# CH3-Input.net
KiCad netlist of a schematic drawn in Altium Designer
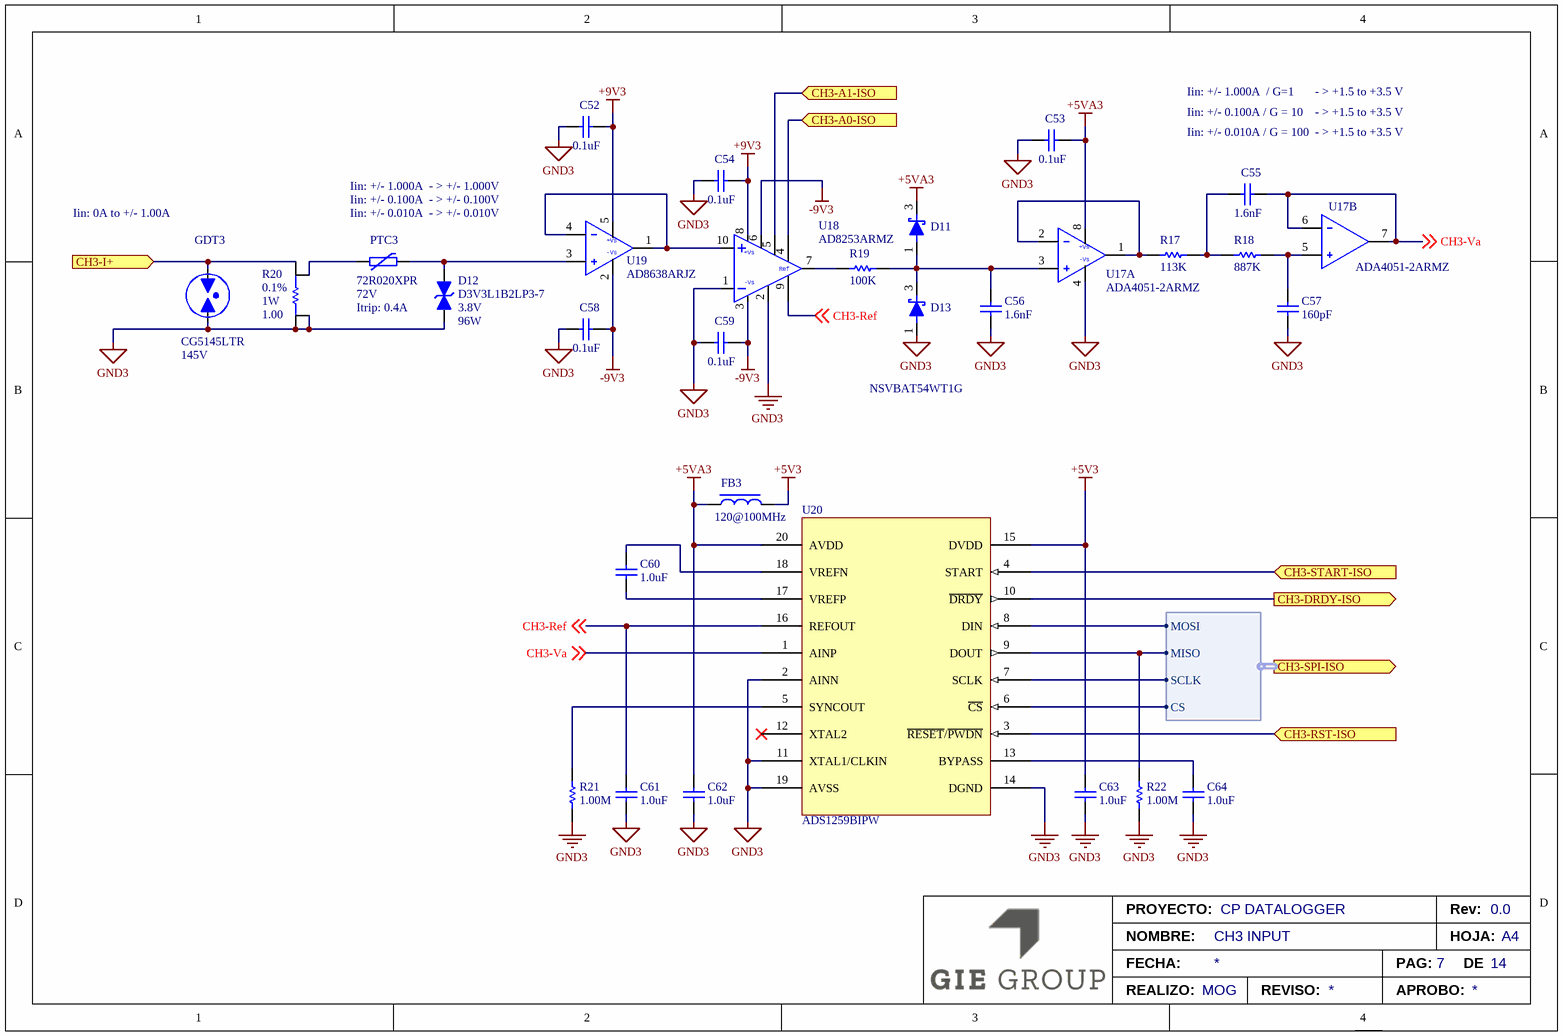
[diagram p0: CH3-Input.SchDoc]

(export (version "E")
  (design (tool "Eeschema 10.0.6"))
  (components
    (comp (ref "C52")
      (value "0.1uF")
      (footprint "CAP-0603")
      (description "CAP CER 0.1uF 50V X7R 0603")
      (fields (field (name "PARTNUMBER") "C0603C104K5RACAUTO") (field (name "MANUFACTURER") "Kemet"))
      (libsource (lib "Kemet") (part "C0603C104K5RACAUTO"))
    )
    (comp (ref "C53")
      (value "0.1uF")
      (footprint "CAP-0603")
      (description "CAP CER 0.1uF 50V X7R 0603")
      (fields (field (name "PARTNUMBER") "C0603C104K5RACAUTO") (field (name "MANUFACTURER") "Kemet"))
      (libsource (lib "Kemet") (part "C0603C104K5RACAUTO"))
    )
    (comp (ref "C54")
      (value "0.1uF")
      (footprint "CAP-0603")
      (description "CAP CER 0.1uF 50V X7R 0603")
      (fields (field (name "PARTNUMBER") "C0603C104K5RACAUTO") (field (name "MANUFACTURER") "Kemet"))
      (libsource (lib "Kemet") (part "C0603C104K5RACAUTO"))
    )
    (comp (ref "C55")
      (value "1.6nF")
      (footprint "CAP-0603")
      (description "CAP CER 1600´pF 50V C0G 0603")
      (fields (field (name "PARTNUMBER") "C0603C162J5GAC7867") (field (name "MANUFACTURER") "Kemet"))
      (libsource (lib "Kemet") (part "C0603C162J5GAC7867"))
    )
    (comp (ref "C56")
      (value "1.6nF")
      (footprint "CAP-0603")
      (description "CAP CER 1600´pF 50V C0G 0603")
      (fields (field (name "PARTNUMBER") "C0603C162J5GAC7867") (field (name "MANUFACTURER") "Kemet"))
      (libsource (lib "Kemet") (part "C0603C162J5GAC7867"))
    )
    (comp (ref "C57")
      (value "160pF")
      (footprint "CAP-0603")
      (description "CAP CER 160 pF 100V C0G 0603")
      (fields (field (name "PARTNUMBER") "C0603C161J1GAC7867") (field (name "MANUFACTURER") "Kemet"))
      (libsource (lib "Kemet") (part "C0603C161J1GAC7867"))
    )
    (comp (ref "C58")
      (value "0.1uF")
      (footprint "CAP-0603")
      (description "CAP CER 0.1uF 50V X7R 0603")
      (fields (field (name "PARTNUMBER") "C0603C104K5RACAUTO") (field (name "MANUFACTURER") "Kemet"))
      (libsource (lib "Kemet") (part "C0603C104K5RACAUTO"))
    )
    (comp (ref "C59")
      (value "0.1uF")
      (footprint "CAP-0603")
      (description "CAP CER 0.1uF 50V X7R 0603")
      (fields (field (name "PARTNUMBER") "C0603C104K5RACAUTO") (field (name "MANUFACTURER") "Kemet"))
      (libsource (lib "Kemet") (part "C0603C104K5RACAUTO"))
    )
    (comp (ref "C60")
      (value "1.0uF")
      (footprint "CAP-0603")
      (description "CAP CER 1uF 25V X7R 0603")
      (fields (field (name "PARTNUMBER") "C0603C105M3RAC7867") (field (name "MANUFACTURER") "Kemet"))
      (libsource (lib "Kemet") (part "C0603C105M3RAC7867"))
    )
    (comp (ref "C61")
      (value "1.0uF")
      (footprint "CAP-0603")
      (description "CAP CER 1uF 25V X7R 0603")
      (fields (field (name "PARTNUMBER") "C0603C105M3RAC7867") (field (name "MANUFACTURER") "Kemet"))
      (libsource (lib "Kemet") (part "C0603C105M3RAC7867"))
    )
    (comp (ref "C62")
      (value "1.0uF")
      (footprint "CAP-0603")
      (description "CAP CER 1uF 25V X7R 0603")
      (fields (field (name "PARTNUMBER") "C0603C105M3RAC7867") (field (name "MANUFACTURER") "Kemet"))
      (libsource (lib "Kemet") (part "C0603C105M3RAC7867"))
    )
    (comp (ref "C63")
      (value "1.0uF")
      (footprint "CAP-0603")
      (description "CAP CER 1uF 25V X7R 0603")
      (fields (field (name "PARTNUMBER") "C0603C105M3RAC7867") (field (name "MANUFACTURER") "Kemet"))
      (libsource (lib "Kemet") (part "C0603C105M3RAC7867"))
    )
    (comp (ref "C64")
      (value "1.0uF")
      (footprint "CAP-0603")
      (description "CAP CER 1uF 25V X7R 0603")
      (fields (field (name "PARTNUMBER") "C0603C105M3RAC7867") (field (name "MANUFACTURER") "Kemet"))
      (libsource (lib "Kemet") (part "C0603C105M3RAC7867"))
    )
    (comp (ref "D11")
      (value "NSVBAT54WT1G")
      (footprint "SOT-323-3")
      (description "Schottky Diode 30V 200mA SOT323")
      (fields (field (name "MANUFACTURER") "OnSemiconductor"))
      (libsource (lib "OnSemiconductors") (part "NSVBAT54WT1G"))
    )
    (comp (ref "D12")
      (value "D3V3L1B2LP3-7")
      (footprint "DIODE-0603")
      (description "TVS Diode 1.5kW 130V 5% Bi-Directional")
      (fields
        (field (name "MANUFACTURER") "Diodes Inc")
        (field (name "PARTNUMBER") "D3V3L1B2LP3-7")
        (field (name "VOLTAGE") "3.8V")
        (field (name "POWER") "96W")
      )
      (libsource (lib "DidesInc") (part "D3V3L1B2LP3-7"))
    )
    (comp (ref "D13")
      (value "NSVBAT54WT1G")
      (footprint "SOT-323-3")
      (description "Schottky Diode 30V 200mA SOT323")
      (fields (field (name "MANUFACTURER") "OnSemiconductor") (field (name "PARTNUMBER") "NSVBAT54WT1G"))
      (libsource (lib "OnSemiconductors") (part "NSVBAT54WT1G"))
    )
    (comp (ref "FB3")
      (value "120@100MHz")
      (footprint "IND-0603")
      (description "Ferrite Bead 120Ohms 900mA 25% DCR=130m")
      (fields (field (name "MANUFACTURER") "Kemet") (field (name "PARTNUMBER") "Z0603C121GPWZT"))
      (libsource (lib "Kemet") (part "Z0603C121GPWZT"))
    )
    (comp (ref "GDT3")
      (value "CG5145LTR")
      (footprint "LITTLELFUSE-CG5XXXLTR")
      (description "Gas Discharge Tube 145V")
      (fields
        (field (name "MANUFACTURER") "Littelfuse")
        (field (name "PARTNUMBER") "CG5145LTR")
        (field (name "VOLTAGE") "145V")
      )
      (libsource (lib "Littlelfuse") (part "CG5145LTR"))
    )
    (comp (ref "PTC3")
      (value "72R020XPR")
      (footprint "LITTLELFUSE-72R020X")
      (description "PTC Polyfuse Radial 72V 0.2A")
      (fields
        (field (name "MANUFACTURER") "Littlelfuse")
        (field (name "PARTNUMBER") "72R020XPR")
        (field (name "VOLTAGE") "72V")
        (field (name "ITRIP") "0.4A")
      )
      (libsource (lib "Littlelfuse") (part "72R020XPR"))
    )
    (comp (ref "R17")
      (value "113K")
      (footprint "RES-0603")
      (description "RES SMD 113K OHM 1% 1/10W 0603")
      (fields (field (name "TOLERANCE") "1%") (field (name "MANUFACTURER") "Yageo"))
      (libsource (lib "Yageo") (part "RC0603FR-07113KL"))
    )
    (comp (ref "R18")
      (value "887K")
      (footprint "RES-0603")
      (description "RES SMD 887K OHM 1% 1/10W 0603")
      (fields (field (name "TOLERANCE") "1%") (field (name "MANUFACTURER") "Yageo"))
      (libsource (lib "Yageo") (part "RC0603FR-07887KL"))
    )
    (comp (ref "R19")
      (value "100K")
      (footprint "RES-0603")
      (description "RES SMD 100K OHM 1% 1/10W 0603")
      (fields (field (name "TOLERANCE") "1%") (field (name "MANUFACTURER") "Yageo"))
      (libsource (lib "Yageo") (part "RC0603FR-07100KL"))
    )
    (comp (ref "R20")
      (value "1.00")
      (footprint "RES-2512 WIDE")
      (description "RES SMD 1 OHM 1W 2516 WIDE")
      (fields
        (field (name "MANUFACTURER") "Vishay")
        (field (name "PARTNUMBER") "Y16061R00000B9W")
        (field (name "TOLERANCE") "0.1%")
        (field (name "POWER") "1W")
      )
      (libsource (lib "Vishay") (part "Y16061R00000B9W"))
    )
    (comp (ref "R21")
      (value "1.00M")
      (footprint "RES-0603")
      (description "RES SMD 1M OHM 1% 1/10W 0603")
      (fields (field (name "TOLERANCE") "1%") (field (name "MANUFACTURER") "Yageo"))
      (libsource (lib "Yageo") (part "RC0603FR-071ML"))
    )
    (comp (ref "R22")
      (value "1.00M")
      (footprint "RES-0603")
      (description "RES SMD 1M OHM 1% 1/10W 0603")
      (fields (field (name "TOLERANCE") "1%") (field (name "MANUFACTURER") "Yageo"))
      (libsource (lib "Yageo") (part "RC0603FR-071ML"))
    )
    (comp (ref "U17")
      (value "ADA4051-2ARMZ")
      (footprint "MSOP8")
      (description "Dual  Precision Amplifier Micro Power Auto Zero")
      (fields (field (name "MANUFACTURER") "Analog Devices") (field (name "PARTNUMBER") "ADA4051-2ARMZ"))
      (libsource (lib "AnalogDevices") (part "ADA4051-2ARMZ"))
    )
    (comp (ref "U18")
      (value "AD8253ARMZ")
      (footprint "MSOP10")
      (description "Instrumentation Amplifiers High Speed Programmable High Gain In-Amp")
      (fields (field (name "MANUFACTURER") "Analog Devices Inc"))
      (libsource (lib "AnalogDevices") (part "AD8253ARMZ"))
    )
    (comp (ref "U19")
      (value "AD8638ARJZ")
      (footprint "SOT23-5")
      (description "16V Auto-Zero CMOS Amplifier")
      (fields (field (name "MANUFACTURER") "Analog Devices") (field (name "PARTNUMBER") "AD8638ARJZ"))
      (libsource (lib "AnalogDevices") (part "AD8638ARJZ"))
    )
    (comp (ref "U20")
      (value "ADS1259BIPW")
      (footprint "TSSOP20")
      (description "Analog to Digital Converter 14.4kSPS 24-Bit")
      (fields (field (name "MANUFACTURER") "Texas Instruments") (field (name "PARTNUMBER") "ADS1259BIPW"))
      (libsource (lib "TexasInstruments") (part "ADS1259BIPW"))
    )
  )
  (nets
    (net (code "2") (name "+5V3") (class "Default")
      (node (ref "C63") (pin "2") (pinfunction "2_2") (pintype "passive"))
      (node (ref "FB3") (pin "2") (pinfunction "2_2") (pintype "passive"))
      (node (ref "U20") (pin "15") (pinfunction "DVDD_15") (pintype "power_in"))
    )
    (net (code "3") (name "+5VA3") (class "Default")
      (node (ref "C53") (pin "2") (pinfunction "2_2") (pintype "passive"))
      (node (ref "C62") (pin "2") (pinfunction "2_2") (pintype "passive"))
      (node (ref "D11") (pin "3") (pinfunction "K_3") (pintype "passive"))
      (node (ref "FB3") (pin "1") (pinfunction "1_1") (pintype "passive"))
      (node (ref "U17") (pin "8") (pinfunction "+VS_8") (pintype "power_in"))
      (node (ref "U20") (pin "20") (pinfunction "AVDD_20") (pintype "power_in"))
    )
    (net (code "4") (name "+9V3") (class "Default")
      (node (ref "C52") (pin "2") (pinfunction "2_2") (pintype "passive"))
      (node (ref "C54") (pin "2") (pinfunction "2_2") (pintype "passive"))
      (node (ref "U18") (pin "8") (pinfunction "+Vs_8") (pintype "passive"))
      (node (ref "U19") (pin "5") (pinfunction "+VS_5") (pintype "power_in"))
    )
    (net (code "5") (name "-9V3") (class "Default")
      (node (ref "C58") (pin "2") (pinfunction "2_2") (pintype "passive"))
      (node (ref "C59") (pin "2") (pinfunction "2_2") (pintype "passive"))
      (node (ref "U18") (pin "3") (pinfunction "-Vs_3") (pintype "passive"))
      (node (ref "U18") (pin "6") (pinfunction "WR_6") (pintype "passive"))
      (node (ref "U19") (pin "2") (pinfunction "-Vs_2") (pintype "power_in"))
    )
    (net (code "6") (name "/CH3-A0-ISO") (class "Default")
      (node (ref "U18") (pin "4") (pinfunction "A0_4") (pintype "passive"))
    )
    (net (code "7") (name "/CH3-A1-ISO") (class "Default")
      (node (ref "U18") (pin "5") (pinfunction "A1_5") (pintype "passive"))
    )
    (net (code "8") (name "/CH3-DRDY-ISO") (class "Default")
      (node (ref "U20") (pin "10") (pinfunction "~{DRDY}_10") (pintype "output"))
    )
    (net (code "9") (name "/CH3-I+") (class "Default")
      (node (ref "GDT3") (pin "1") (pinfunction "A_1") (pintype "passive"))
      (node (ref "R20") (pin "I1") (pinfunction "1_I1") (pintype "passive"))
    )
    (net (code "10") (name "/CH3-RST-ISO") (class "Default")
      (node (ref "U20") (pin "3") (pinfunction "~{RESET}/~{PWDN}_3") (pintype "input"))
    )
    (net (code "11") (name "/CH3-START-ISO") (class "Default")
      (node (ref "U20") (pin "4") (pinfunction "START_4") (pintype "input"))
    )
    (net (code "12") (name "/CS") (class "Default")
      (node (ref "U20") (pin "6") (pinfunction "~{CS}_6") (pintype "input"))
    )
    (net (code "13") (name "/MISO") (class "Default")
      (node (ref "R22") (pin "2") (pinfunction "2_2") (pintype "passive"))
      (node (ref "U20") (pin "9") (pinfunction "DOUT_9") (pintype "output"))
    )
    (net (code "14") (name "/MOSI") (class "Default")
      (node (ref "U20") (pin "8") (pinfunction "DIN_8") (pintype "input"))
    )
    (net (code "15") (name "/SCLK") (class "Default")
      (node (ref "U20") (pin "7") (pinfunction "SCLK_7") (pintype "input"))
    )
    (net (code "17") (name "CH3-Ref") (class "Default")
      (node (ref "C61") (pin "2") (pinfunction "2_2") (pintype "passive"))
      (node (ref "U18") (pin "9") (pinfunction "REF_9") (pintype "passive"))
      (node (ref "U20") (pin "16") (pinfunction "REFOUT_16") (pintype "power_in"))
    )
    (net (code "18") (name "CH3-Va") (class "Default")
      (node (ref "C55") (pin "1") (pinfunction "1_1") (pintype "passive"))
      (node (ref "U17") (pin "6") (pinfunction "-INB_6") (pintype "passive"))
      (node (ref "U17") (pin "7") (pinfunction "OUTB_7") (pintype "passive"))
      (node (ref "U20") (pin "1") (pinfunction "AINP_1") (pintype "passive"))
    )
    (net (code "19") (name "GND3") (class "Default")
      (node (ref "C52") (pin "1") (pinfunction "1_1") (pintype "passive"))
      (node (ref "C53") (pin "1") (pinfunction "1_1") (pintype "passive"))
      (node (ref "C54") (pin "1") (pinfunction "1_1") (pintype "passive"))
      (node (ref "C56") (pin "1") (pinfunction "1_1") (pintype "passive"))
      (node (ref "C57") (pin "1") (pinfunction "1_1") (pintype "passive"))
      (node (ref "C58") (pin "1") (pinfunction "1_1") (pintype "passive"))
      (node (ref "C59") (pin "1") (pinfunction "1_1") (pintype "passive"))
      (node (ref "C61") (pin "1") (pinfunction "1_1") (pintype "passive"))
      (node (ref "C62") (pin "1") (pinfunction "1_1") (pintype "passive"))
      (node (ref "C63") (pin "1") (pinfunction "1_1") (pintype "passive"))
      (node (ref "C64") (pin "1") (pinfunction "1_1") (pintype "passive"))
      (node (ref "D12") (pin "2") (pinfunction "K_2") (pintype "passive"))
      (node (ref "D13") (pin "1") (pinfunction "A_1") (pintype "passive"))
      (node (ref "GDT3") (pin "2") (pinfunction "K_2") (pintype "passive"))
      (node (ref "R20") (pin "E2") (pinfunction "1_E2") (pintype "passive"))
      (node (ref "R20") (pin "I2") (pinfunction "2_I2") (pintype "passive"))
      (node (ref "R21") (pin "1") (pinfunction "1_1") (pintype "passive"))
      (node (ref "R22") (pin "1") (pinfunction "1_1") (pintype "passive"))
      (node (ref "U17") (pin "4") (pinfunction "-Vs_4") (pintype "power_in"))
      (node (ref "U18") (pin "1") (pinfunction "-_IN_1") (pintype "passive"))
      (node (ref "U18") (pin "2") (pinfunction "DGND_2") (pintype "passive"))
      (node (ref "U20") (pin "11") (pinfunction "XTAL1/CLKIN_11") (pintype "power_in"))
      (node (ref "U20") (pin "14") (pinfunction "DGND_14") (pintype "power_in"))
      (node (ref "U20") (pin "19") (pinfunction "AVSS_19") (pintype "power_in"))
      (node (ref "U20") (pin "2") (pinfunction "AINN_2") (pintype "passive"))
    )
    (net (code "20") (name "Net-(C55-Pad2)") (class "Default")
      (node (ref "C55") (pin "2") (pinfunction "2_2") (pintype "passive"))
      (node (ref "R17") (pin "2") (pinfunction "2_2") (pintype "passive"))
      (node (ref "R18") (pin "1") (pinfunction "1_1") (pintype "passive"))
    )
    (net (code "21") (name "Net-(D11-A)") (class "Default")
      (node (ref "C56") (pin "2") (pinfunction "2_2") (pintype "passive"))
      (node (ref "D11") (pin "1") (pinfunction "A_1") (pintype "passive"))
      (node (ref "D13") (pin "3") (pinfunction "K_3") (pintype "passive"))
      (node (ref "R19") (pin "2") (pinfunction "2_2") (pintype "passive"))
      (node (ref "U17") (pin "3") (pinfunction "+INA_3") (pintype "passive"))
    )
    (net (code "22") (name "Net-(D12-A)") (class "Default")
      (node (ref "D12") (pin "1") (pinfunction "A_1") (pintype "passive"))
      (node (ref "PTC3") (pin "2") (pinfunction "2_2") (pintype "passive"))
      (node (ref "U19") (pin "3") (pinfunction "+IN_3") (pintype "passive"))
    )
    (net (code "23") (name "Net-(PTC3-Pad1)") (class "Default")
      (node (ref "PTC3") (pin "1") (pinfunction "1_1") (pintype "passive"))
      (node (ref "R20") (pin "E1") (pinfunction "1_E1") (pintype "passive"))
    )
    (net (code "24") (name "Net-(U17A--INA)") (class "Default")
      (node (ref "R17") (pin "1") (pinfunction "1_1") (pintype "passive"))
      (node (ref "U17") (pin "1") (pinfunction "OUTA_1") (pintype "passive"))
      (node (ref "U17") (pin "2") (pinfunction "-INA_2") (pintype "passive"))
    )
    (net (code "25") (name "Net-(U17B-+INB)") (class "Default")
      (node (ref "C57") (pin "2") (pinfunction "2_2") (pintype "passive"))
      (node (ref "R18") (pin "2") (pinfunction "2_2") (pintype "passive"))
      (node (ref "U17") (pin "5") (pinfunction "+INB_5") (pintype "passive"))
    )
    (net (code "26") (name "Net-(U18-+_IN)") (class "Default")
      (node (ref "U18") (pin "10") (pinfunction "+_IN_10") (pintype "passive"))
      (node (ref "U19") (pin "1") (pinfunction "OUT_1") (pintype "passive"))
      (node (ref "U19") (pin "4") (pinfunction "-IN_4") (pintype "passive"))
    )
    (net (code "27") (name "Net-(U18-OUT)") (class "Default")
      (node (ref "R19") (pin "1") (pinfunction "1_1") (pintype "passive"))
      (node (ref "U18") (pin "7") (pinfunction "OUT_7") (pintype "passive"))
    )
    (net (code "28") (name "Net-(U20-BYPASS)") (class "Default")
      (node (ref "C64") (pin "2") (pinfunction "2_2") (pintype "passive"))
      (node (ref "U20") (pin "13") (pinfunction "BYPASS_13") (pintype "power_in"))
    )
    (net (code "29") (name "Net-(U20-SYNCOUT)") (class "Default")
      (node (ref "R21") (pin "2") (pinfunction "2_2") (pintype "passive"))
      (node (ref "U20") (pin "5") (pinfunction "SYNCOUT_5") (pintype "passive"))
    )
    (net (code "30") (name "Net-(U20-VREFN)") (class "Default")
      (node (ref "C60") (pin "2") (pinfunction "2_2") (pintype "passive"))
      (node (ref "U20") (pin "18") (pinfunction "VREFN_18") (pintype "power_in"))
    )
    (net (code "31") (name "Net-(U20-VREFP)") (class "Default")
      (node (ref "C60") (pin "1") (pinfunction "1_1") (pintype "passive"))
      (node (ref "U20") (pin "17") (pinfunction "VREFP_17") (pintype "power_in"))
    )
    (net (code "32") (name "unconnected-(U20-XTAL2-Pad12)") (class "Default")
      (node (ref "U20") (pin "12") (pinfunction "XTAL2_12") (pintype "power_in+no_connect"))
    )
  )
)
